# MagSpark.net
KiCad netlist of a schematic drawn in EAGLE
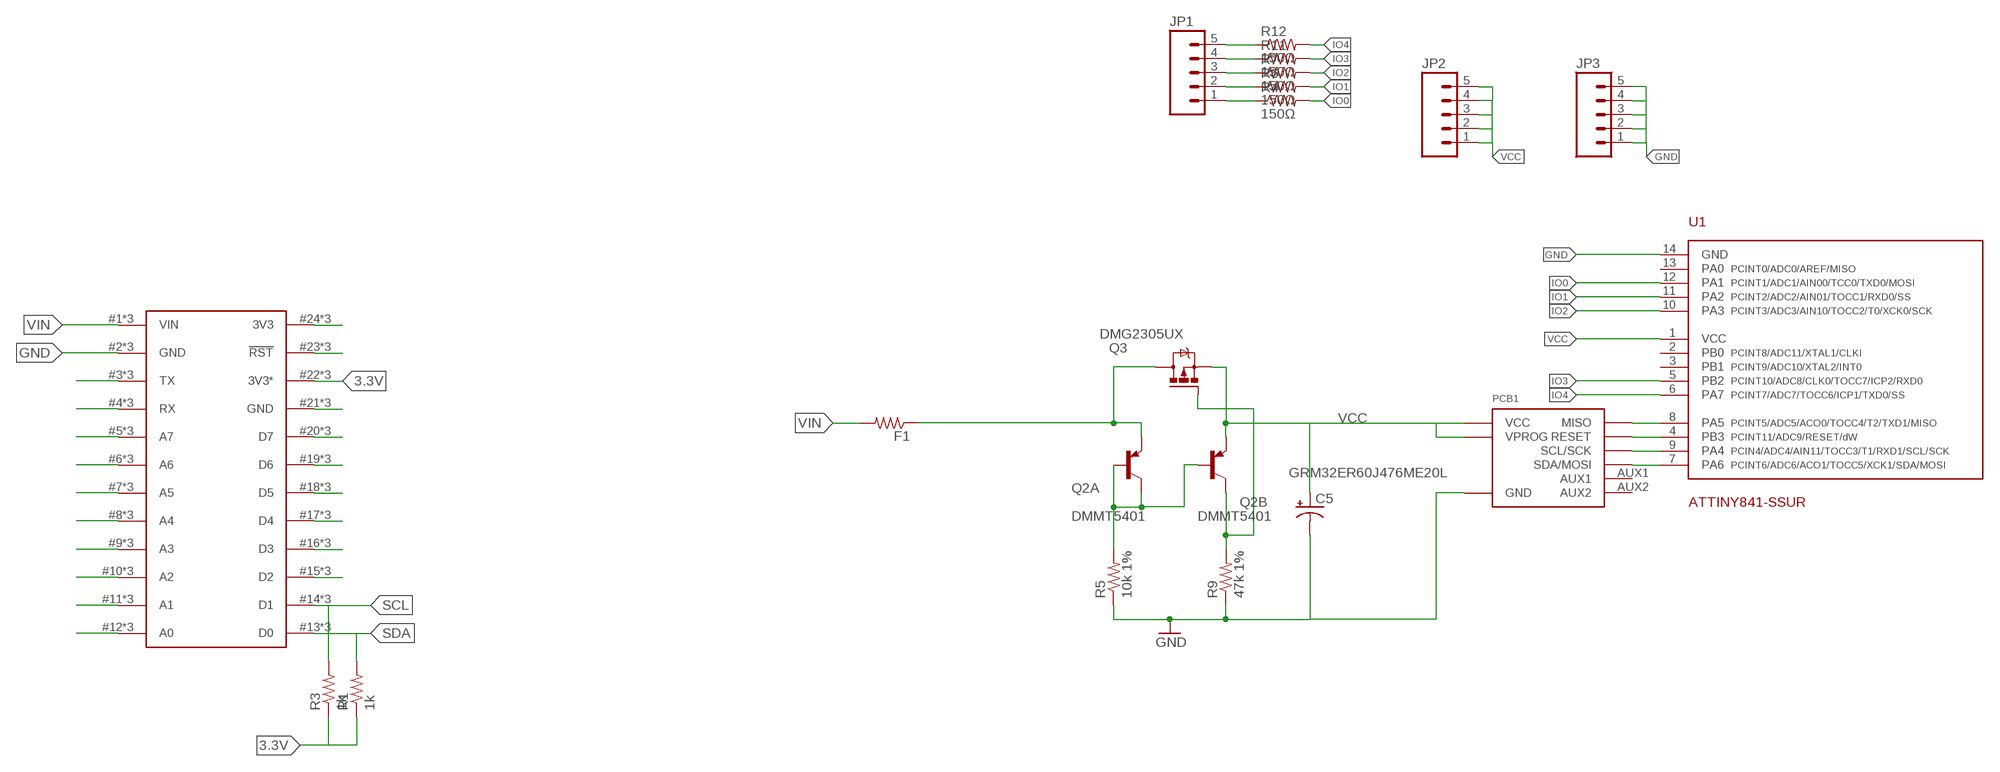
[diagram p0: schematic, sheet 1]

(export (version "E")
  (design (tool "Eeschema 10.0.6"))
  (components
    (comp (ref "C5")
      (value "CAP_POLC")
      (footprint "eagle-import:PANASONIC_C")
      (libsource (lib "eagle-import") (part "CAP_POLC"))
    )
    (comp (ref "F1")
      (value "RESISTOR0805-RES")
      (footprint "eagle-import:0805")
      (libsource (lib "eagle-import") (part "RESISTOR0805-RES"))
    )
    (comp (ref "JP1")
      (value "M05NO_SILK")
      (footprint "eagle-import:1X05_NO_SILK")
      (libsource (lib "eagle-import") (part "M05NO_SILK"))
    )
    (comp (ref "JP2")
      (value "M05NO_SILK")
      (footprint "eagle-import:1X05_NO_SILK")
      (libsource (lib "eagle-import") (part "M05NO_SILK"))
    )
    (comp (ref "JP3")
      (value "M05NO_SILK")
      (footprint "eagle-import:1X05_NO_SILK")
      (libsource (lib "eagle-import") (part "M05NO_SILK"))
    )
    (comp (ref "PCB1")
      (value "MAGDEVICE-V2-DOUBLE")
      (footprint "eagle-import:MAGDEVICE-V2-DOUBLE")
      (libsource (lib "eagle-import") (part "MAGDEVICE-V2-DOUBLE"))
    )
    (comp (ref "Q2")
      (value "DMMT5401")
      (footprint "eagle-import:SOT-26")
      (libsource (lib "eagle-import") (part "TRANSISTOR-DUAL-PNP"))
    )
    (comp (ref "Q3")
      (value "DMG2305UX")
      (footprint "eagle-import:MICRO3")
      (libsource (lib "eagle-import") (part "IRLML5203"))
    )
    (comp (ref "R1")
      (value "1k")
      (footprint "eagle-import:0805")
      (libsource (lib "eagle-import") (part "RESISTOR0805-RES"))
    )
    (comp (ref "R3")
      (value "1k")
      (footprint "eagle-import:0805")
      (libsource (lib "eagle-import") (part "RESISTOR0805-RES"))
    )
    (comp (ref "R4")
      (value "150Ω")
      (footprint "eagle-import:0603")
      (fields (field (name "PARTNUM") "ERJ-3EKF1500V"))
      (libsource (lib "eagle-import") (part "RESISTOR-150Ω"))
    )
    (comp (ref "R5")
      (value "10k 1%")
      (footprint "eagle-import:0805")
      (libsource (lib "eagle-import") (part "RESISTOR0805-RES"))
    )
    (comp (ref "R6")
      (value "150Ω")
      (footprint "eagle-import:0603")
      (fields (field (name "PARTNUM") "ERJ-3EKF1500V"))
      (libsource (lib "eagle-import") (part "RESISTOR-150Ω"))
    )
    (comp (ref "R7")
      (value "150Ω")
      (footprint "eagle-import:0603")
      (fields (field (name "PARTNUM") "ERJ-3EKF1500V"))
      (libsource (lib "eagle-import") (part "RESISTOR-150Ω"))
    )
    (comp (ref "R9")
      (value "47k 1%")
      (footprint "eagle-import:0805")
      (libsource (lib "eagle-import") (part "RESISTOR0805-RES"))
    )
    (comp (ref "R11")
      (value "150Ω")
      (footprint "eagle-import:0603")
      (fields (field (name "PARTNUM") "ERJ-3EKF1500V"))
      (libsource (lib "eagle-import") (part "RESISTOR-150Ω"))
    )
    (comp (ref "R12")
      (value "150Ω")
      (footprint "eagle-import:0603")
      (fields (field (name "PARTNUM") "ERJ-3EKF1500V"))
      (libsource (lib "eagle-import") (part "RESISTOR-150Ω"))
    )
    (comp (ref "U$2")
      (value "SPARK_CORE")
      (footprint "eagle-import:SPARK_CORE_STACKABLE")
      (libsource (lib "eagle-import") (part "SPARK_CORE"))
    )
    (comp (ref "U1")
      (value "ATTINY841-SSUR")
      (footprint "eagle-import:SOIC-14")
      (libsource (lib "eagle-import") (part "ATTINY841"))
    )
  )
  (nets
    (net (code "1") (name "3.3V") (class "Default")
      (node (ref "R1") (pin "1") (pinfunction "1_1") (pintype "passive"))
      (node (ref "R3") (pin "1") (pinfunction "1_1") (pintype "passive"))
      (node (ref "U$2") (pin "#22") (pinfunction "3V3*_#22") (pintype "power_in"))
      (node (ref "U$2") (pin "22") (pinfunction "3V3*_22") (pintype "power_in"))
      (node (ref "U$2") (pin "@22") (pinfunction "3V3*_@22") (pintype "power_in"))
    )
    (net (code "2") (name "GND") (class "Default")
      (node (ref "C5") (pin "-") (pinfunction "-_-") (pintype "passive"))
      (node (ref "JP3") (pin "1") (pinfunction "1_1") (pintype "passive"))
      (node (ref "JP3") (pin "2") (pinfunction "2_2") (pintype "passive"))
      (node (ref "JP3") (pin "3") (pinfunction "3_3") (pintype "passive"))
      (node (ref "JP3") (pin "4") (pinfunction "4_4") (pintype "passive"))
      (node (ref "JP3") (pin "5") (pinfunction "5_5") (pintype "passive"))
      (node (ref "PCB1") (pin "GND") (pinfunction "GND_GND") (pintype "bidirectional"))
      (node (ref "R5") (pin "1") (pinfunction "1_1") (pintype "passive"))
      (node (ref "R9") (pin "1") (pinfunction "1_1") (pintype "passive"))
      (node (ref "U$2") (pin "#2") (pinfunction "GND_#2") (pintype "power_in"))
      (node (ref "U$2") (pin "2") (pinfunction "GND_2") (pintype "power_in"))
      (node (ref "U$2") (pin "@2") (pinfunction "GND_@2") (pintype "power_in"))
      (node (ref "U1") (pin "14") (pinfunction "GND_14") (pintype "bidirectional"))
    )
    (net (code "3") (name "IO0") (class "Default")
      (node (ref "R4") (pin "2") (pinfunction "2_2") (pintype "passive"))
      (node (ref "U1") (pin "12") (pinfunction "PA1_12") (pintype "bidirectional"))
    )
    (net (code "4") (name "IO1") (class "Default")
      (node (ref "R6") (pin "2") (pinfunction "2_2") (pintype "passive"))
      (node (ref "U1") (pin "11") (pinfunction "PA2_11") (pintype "bidirectional"))
    )
    (net (code "5") (name "IO2") (class "Default")
      (node (ref "R7") (pin "2") (pinfunction "2_2") (pintype "passive"))
      (node (ref "U1") (pin "10") (pinfunction "PA3_10") (pintype "bidirectional"))
    )
    (net (code "6") (name "IO3") (class "Default")
      (node (ref "R11") (pin "2") (pinfunction "2_2") (pintype "passive"))
      (node (ref "U1") (pin "5") (pinfunction "PB2_5") (pintype "bidirectional"))
    )
    (net (code "7") (name "IO4") (class "Default")
      (node (ref "R12") (pin "2") (pinfunction "2_2") (pintype "passive"))
      (node (ref "U1") (pin "6") (pinfunction "PA7_6") (pintype "bidirectional"))
    )
    (net (code "8") (name "Net-(JP1-Pad1)") (class "Default")
      (node (ref "JP1") (pin "1") (pinfunction "1_1") (pintype "passive"))
      (node (ref "R4") (pin "1") (pinfunction "1_1") (pintype "passive"))
    )
    (net (code "9") (name "Net-(JP1-Pad2)") (class "Default")
      (node (ref "JP1") (pin "2") (pinfunction "2_2") (pintype "passive"))
      (node (ref "R6") (pin "1") (pinfunction "1_1") (pintype "passive"))
    )
    (net (code "10") (name "Net-(JP1-Pad3)") (class "Default")
      (node (ref "JP1") (pin "3") (pinfunction "3_3") (pintype "passive"))
      (node (ref "R7") (pin "1") (pinfunction "1_1") (pintype "passive"))
    )
    (net (code "11") (name "Net-(JP1-Pad4)") (class "Default")
      (node (ref "JP1") (pin "4") (pinfunction "4_4") (pintype "passive"))
      (node (ref "R11") (pin "1") (pinfunction "1_1") (pintype "passive"))
    )
    (net (code "12") (name "Net-(JP1-Pad5)") (class "Default")
      (node (ref "JP1") (pin "5") (pinfunction "5_5") (pintype "passive"))
      (node (ref "R12") (pin "1") (pinfunction "1_1") (pintype "passive"))
    )
    (net (code "13") (name "Net-(PCB1-SCL{slash}SCK)") (class "Default")
      (node (ref "PCB1") (pin "SCL") (pinfunction "SCL/SCK_SCL") (pintype "bidirectional"))
      (node (ref "U1") (pin "9") (pinfunction "PA4_9") (pintype "bidirectional"))
    )
    (net (code "14") (name "Net-(PCB1-SDA{slash}MOSI)") (class "Default")
      (node (ref "PCB1") (pin "SDA") (pinfunction "SDA/MOSI_SDA") (pintype "bidirectional"))
      (node (ref "U1") (pin "7") (pinfunction "PA6_7") (pintype "bidirectional"))
    )
    (net (code "15") (name "Net-(Q2A-B)") (class "Default")
      (node (ref "Q2") (pin "1") (pinfunction "C_1") (pintype "passive"))
      (node (ref "Q2") (pin "2") (pinfunction "B_2") (pintype "passive"))
      (node (ref "Q2") (pin "3") (pinfunction "B_3") (pintype "passive"))
      (node (ref "R5") (pin "2") (pinfunction "2_2") (pintype "passive"))
    )
    (net (code "16") (name "Net-(Q2A-E)") (class "Default")
      (node (ref "F1") (pin "1") (pinfunction "1_1") (pintype "passive"))
      (node (ref "Q2") (pin "6") (pinfunction "E_6") (pintype "passive"))
      (node (ref "Q3") (pin "3") (pinfunction "D_3") (pintype "passive"))
    )
    (net (code "17") (name "Net-(Q2B-C)") (class "Default")
      (node (ref "Q2") (pin "4") (pinfunction "C_4") (pintype "passive"))
      (node (ref "Q3") (pin "1") (pinfunction "G_1") (pintype "passive"))
      (node (ref "R9") (pin "2") (pinfunction "2_2") (pintype "passive"))
    )
    (net (code "18") (name "Net-(U$2-3V3-Pad#24)") (class "Default")
      (node (ref "U$2") (pin "#24") (pinfunction "3V3_#24") (pintype "power_in"))
      (node (ref "U$2") (pin "24") (pinfunction "3V3_24") (pintype "power_in"))
      (node (ref "U$2") (pin "@24") (pinfunction "3V3_@24") (pintype "power_in"))
    )
    (net (code "19") (name "Net-(U$2-A0-Pad#12)") (class "Default")
      (node (ref "U$2") (pin "#12") (pinfunction "A0_#12") (pintype "bidirectional"))
      (node (ref "U$2") (pin "12") (pinfunction "A0_12") (pintype "bidirectional"))
      (node (ref "U$2") (pin "@12") (pinfunction "A0_@12") (pintype "bidirectional"))
    )
    (net (code "20") (name "Net-(U$2-A1-Pad#11)") (class "Default")
      (node (ref "U$2") (pin "#11") (pinfunction "A1_#11") (pintype "bidirectional"))
      (node (ref "U$2") (pin "11") (pinfunction "A1_11") (pintype "bidirectional"))
      (node (ref "U$2") (pin "@11") (pinfunction "A1_@11") (pintype "bidirectional"))
    )
    (net (code "21") (name "Net-(U$2-A2-Pad#10)") (class "Default")
      (node (ref "U$2") (pin "#10") (pinfunction "A2_#10") (pintype "bidirectional"))
      (node (ref "U$2") (pin "10") (pinfunction "A2_10") (pintype "bidirectional"))
      (node (ref "U$2") (pin "@10") (pinfunction "A2_@10") (pintype "bidirectional"))
    )
    (net (code "22") (name "Net-(U$2-A3-Pad#9)") (class "Default")
      (node (ref "U$2") (pin "#9") (pinfunction "A3_#9") (pintype "bidirectional"))
      (node (ref "U$2") (pin "9") (pinfunction "A3_9") (pintype "bidirectional"))
      (node (ref "U$2") (pin "@9") (pinfunction "A3_@9") (pintype "bidirectional"))
    )
    (net (code "23") (name "Net-(U$2-A4-Pad#8)") (class "Default")
      (node (ref "U$2") (pin "#8") (pinfunction "A4_#8") (pintype "bidirectional"))
      (node (ref "U$2") (pin "8") (pinfunction "A4_8") (pintype "bidirectional"))
      (node (ref "U$2") (pin "@8") (pinfunction "A4_@8") (pintype "bidirectional"))
    )
    (net (code "24") (name "Net-(U$2-A5-Pad#7)") (class "Default")
      (node (ref "U$2") (pin "#7") (pinfunction "A5_#7") (pintype "bidirectional"))
      (node (ref "U$2") (pin "7") (pinfunction "A5_7") (pintype "bidirectional"))
      (node (ref "U$2") (pin "@7") (pinfunction "A5_@7") (pintype "bidirectional"))
    )
    (net (code "25") (name "Net-(U$2-A6-Pad#6)") (class "Default")
      (node (ref "U$2") (pin "#6") (pinfunction "A6_#6") (pintype "bidirectional"))
      (node (ref "U$2") (pin "6") (pinfunction "A6_6") (pintype "bidirectional"))
      (node (ref "U$2") (pin "@6") (pinfunction "A6_@6") (pintype "bidirectional"))
    )
    (net (code "26") (name "Net-(U$2-A7-Pad#5)") (class "Default")
      (node (ref "U$2") (pin "#5") (pinfunction "A7_#5") (pintype "bidirectional"))
      (node (ref "U$2") (pin "5") (pinfunction "A7_5") (pintype "bidirectional"))
      (node (ref "U$2") (pin "@5") (pinfunction "A7_@5") (pintype "bidirectional"))
    )
    (net (code "27") (name "Net-(U$2-D2-Pad#15)") (class "Default")
      (node (ref "U$2") (pin "#15") (pinfunction "D2_#15") (pintype "bidirectional"))
      (node (ref "U$2") (pin "15") (pinfunction "D2_15") (pintype "bidirectional"))
      (node (ref "U$2") (pin "@15") (pinfunction "D2_@15") (pintype "bidirectional"))
    )
    (net (code "28") (name "Net-(U$2-D3-Pad#16)") (class "Default")
      (node (ref "U$2") (pin "#16") (pinfunction "D3_#16") (pintype "bidirectional"))
      (node (ref "U$2") (pin "16") (pinfunction "D3_16") (pintype "bidirectional"))
      (node (ref "U$2") (pin "@16") (pinfunction "D3_@16") (pintype "bidirectional"))
    )
    (net (code "29") (name "Net-(U$2-D4-Pad#17)") (class "Default")
      (node (ref "U$2") (pin "#17") (pinfunction "D4_#17") (pintype "bidirectional"))
      (node (ref "U$2") (pin "17") (pinfunction "D4_17") (pintype "bidirectional"))
      (node (ref "U$2") (pin "@17") (pinfunction "D4_@17") (pintype "bidirectional"))
    )
    (net (code "30") (name "Net-(U$2-D5-Pad#18)") (class "Default")
      (node (ref "U$2") (pin "#18") (pinfunction "D5_#18") (pintype "bidirectional"))
      (node (ref "U$2") (pin "18") (pinfunction "D5_18") (pintype "bidirectional"))
      (node (ref "U$2") (pin "@18") (pinfunction "D5_@18") (pintype "bidirectional"))
    )
    (net (code "31") (name "Net-(U$2-D6-Pad#19)") (class "Default")
      (node (ref "U$2") (pin "#19") (pinfunction "D6_#19") (pintype "bidirectional"))
      (node (ref "U$2") (pin "19") (pinfunction "D6_19") (pintype "bidirectional"))
      (node (ref "U$2") (pin "@19") (pinfunction "D6_@19") (pintype "bidirectional"))
    )
    (net (code "32") (name "Net-(U$2-D7-Pad#20)") (class "Default")
      (node (ref "U$2") (pin "#20") (pinfunction "D7_#20") (pintype "bidirectional"))
      (node (ref "U$2") (pin "20") (pinfunction "D7_20") (pintype "bidirectional"))
      (node (ref "U$2") (pin "@20") (pinfunction "D7_@20") (pintype "bidirectional"))
    )
    (net (code "33") (name "Net-(U$2-GND-Pad#21)") (class "Default")
      (node (ref "U$2") (pin "#21") (pinfunction "GND_#21") (pintype "power_in"))
      (node (ref "U$2") (pin "21") (pinfunction "GND_21") (pintype "power_in"))
      (node (ref "U$2") (pin "@21") (pinfunction "GND_@21") (pintype "power_in"))
    )
    (net (code "34") (name "Net-(U$2-RX-Pad#4)") (class "Default")
      (node (ref "U$2") (pin "#4") (pinfunction "RX_#4") (pintype "bidirectional"))
      (node (ref "U$2") (pin "4") (pinfunction "RX_4") (pintype "bidirectional"))
      (node (ref "U$2") (pin "@4") (pinfunction "RX_@4") (pintype "bidirectional"))
    )
    (net (code "35") (name "Net-(U$2-TX-Pad#3)") (class "Default")
      (node (ref "U$2") (pin "#3") (pinfunction "TX_#3") (pintype "bidirectional"))
      (node (ref "U$2") (pin "3") (pinfunction "TX_3") (pintype "bidirectional"))
      (node (ref "U$2") (pin "@3") (pinfunction "TX_@3") (pintype "bidirectional"))
    )
    (net (code "36") (name "Net-(U$2-~{RST}-Pad#23)") (class "Default")
      (node (ref "U$2") (pin "#23") (pinfunction "~{RST}_#23") (pintype "bidirectional"))
      (node (ref "U$2") (pin "23") (pinfunction "~{RST}_23") (pintype "bidirectional"))
      (node (ref "U$2") (pin "@23") (pinfunction "~{RST}_@23") (pintype "bidirectional"))
    )
    (net (code "37") (name "Net-(U1-PA5)") (class "Default")
      (node (ref "PCB1") (pin "MISO") (pinfunction "MISO_MISO") (pintype "bidirectional"))
      (node (ref "U1") (pin "8") (pinfunction "PA5_8") (pintype "bidirectional"))
    )
    (net (code "38") (name "Net-(U1-PB3)") (class "Default")
      (node (ref "PCB1") (pin "RESET") (pinfunction "RESET_RESET") (pintype "bidirectional"))
      (node (ref "U1") (pin "4") (pinfunction "PB3_4") (pintype "bidirectional"))
    )
    (net (code "39") (name "SCL") (class "Default")
      (node (ref "R3") (pin "2") (pinfunction "2_2") (pintype "passive"))
      (node (ref "U$2") (pin "#14") (pinfunction "D1_#14") (pintype "bidirectional"))
      (node (ref "U$2") (pin "14") (pinfunction "D1_14") (pintype "bidirectional"))
      (node (ref "U$2") (pin "@14") (pinfunction "D1_@14") (pintype "bidirectional"))
    )
    (net (code "40") (name "SDA") (class "Default")
      (node (ref "R1") (pin "2") (pinfunction "2_2") (pintype "passive"))
      (node (ref "U$2") (pin "#13") (pinfunction "D0_#13") (pintype "bidirectional"))
      (node (ref "U$2") (pin "13") (pinfunction "D0_13") (pintype "bidirectional"))
      (node (ref "U$2") (pin "@13") (pinfunction "D0_@13") (pintype "bidirectional"))
    )
    (net (code "41") (name "VCC") (class "Default")
      (node (ref "C5") (pin "+") (pinfunction "+_+") (pintype "passive"))
      (node (ref "JP2") (pin "1") (pinfunction "1_1") (pintype "passive"))
      (node (ref "JP2") (pin "2") (pinfunction "2_2") (pintype "passive"))
      (node (ref "JP2") (pin "3") (pinfunction "3_3") (pintype "passive"))
      (node (ref "JP2") (pin "4") (pinfunction "4_4") (pintype "passive"))
      (node (ref "JP2") (pin "5") (pinfunction "5_5") (pintype "passive"))
      (node (ref "PCB1") (pin "VCC") (pinfunction "VCC_VCC") (pintype "bidirectional"))
      (node (ref "PCB1") (pin "VPROG") (pinfunction "VPROG_VPROG") (pintype "bidirectional"))
      (node (ref "Q2") (pin "5") (pinfunction "E_5") (pintype "passive"))
      (node (ref "Q3") (pin "2") (pinfunction "S_2") (pintype "passive"))
      (node (ref "U1") (pin "1") (pinfunction "VCC_1") (pintype "bidirectional"))
    )
    (net (code "42") (name "VIN") (class "Default")
      (node (ref "F1") (pin "2") (pinfunction "2_2") (pintype "passive"))
      (node (ref "U$2") (pin "#1") (pinfunction "VIN_#1") (pintype "power_in"))
      (node (ref "U$2") (pin "1") (pinfunction "VIN_1") (pintype "power_in"))
      (node (ref "U$2") (pin "@1") (pinfunction "VIN_@1") (pintype "power_in"))
    )
    (net (code "43") (name "unconnected-(PCB1-PadAUX1)") (class "Default")
      (node (ref "PCB1") (pin "AUX1") (pinfunction "AUX1_AUX1") (pintype "bidirectional"))
    )
    (net (code "44") (name "unconnected-(PCB1-PadAUX2)") (class "Default")
      (node (ref "PCB1") (pin "AUX2") (pinfunction "AUX2_AUX2") (pintype "bidirectional"))
    )
    (net (code "45") (name "unconnected-(U1-PA0-Pad13)") (class "Default")
      (node (ref "U1") (pin "13") (pinfunction "PA0_13") (pintype "bidirectional"))
    )
    (net (code "46") (name "unconnected-(U1-PB0-Pad2)") (class "Default")
      (node (ref "U1") (pin "2") (pinfunction "PB0_2") (pintype "bidirectional"))
    )
    (net (code "47") (name "unconnected-(U1-PB1-Pad3)") (class "Default")
      (node (ref "U1") (pin "3") (pinfunction "PB1_3") (pintype "bidirectional"))
    )
  )
)
